# atmega16prog.net
KiCad netlist of a schematic drawn in EAGLE
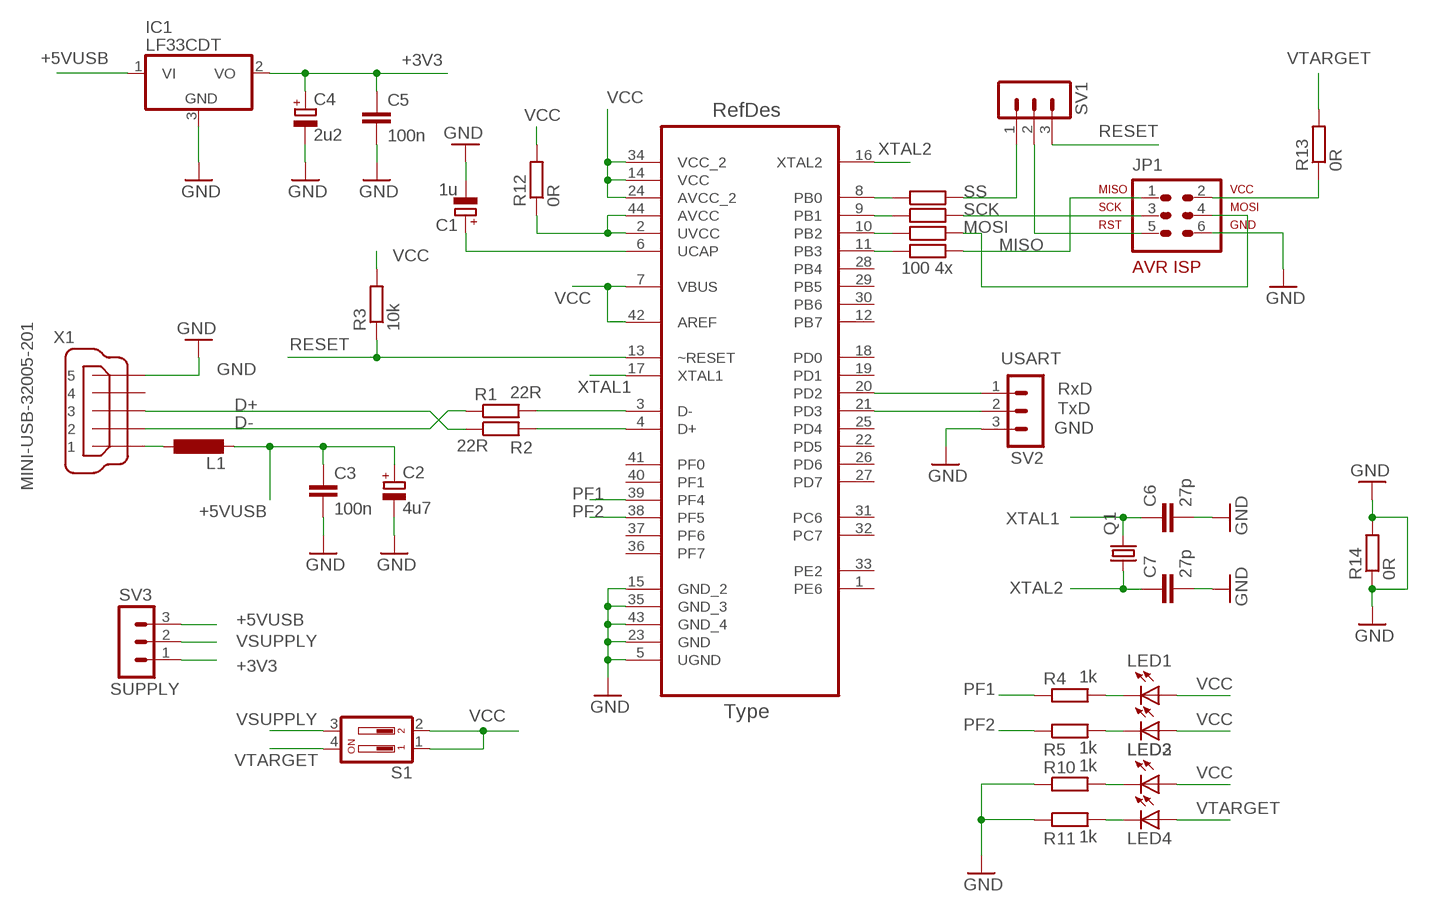
[diagram p0: schematic, sheet 1]

(export (version "E")
  (design (tool "Eeschema 10.0.6"))
  (components
    (comp (ref "C1")
      (value "1u")
      (footprint "eagle-import:SMC_A")
      (libsource (lib "eagle-import") (part "CPOL-EUSMCA"))
    )
    (comp (ref "C2")
      (value "4u7")
      (footprint "eagle-import:SMC_B")
      (libsource (lib "eagle-import") (part "resistor_CPOL-EUSMCB"))
    )
    (comp (ref "C3")
      (value "100n")
      (footprint "eagle-import:C0805K")
      (libsource (lib "eagle-import") (part "C-EUC0805K"))
    )
    (comp (ref "C4")
      (value "2u2")
      (footprint "eagle-import:A_3216-18W")
      (libsource (lib "eagle-import") (part "resistor_CPOL-EUA/3216-18W"))
    )
    (comp (ref "C5")
      (value "100n")
      (footprint "eagle-import:C0805K")
      (libsource (lib "eagle-import") (part "C-EUC0805K"))
    )
    (comp (ref "C6")
      (value "27p")
      (footprint "eagle-import:C0805K")
      (libsource (lib "eagle-import") (part "C-EUC0805K"))
    )
    (comp (ref "C7")
      (value "27p")
      (footprint "eagle-import:C0805K")
      (libsource (lib "eagle-import") (part "C-EUC0805K"))
    )
    (comp (ref "IC1")
      (value "LF33CDT")
      (footprint "eagle-import:TO252")
      (libsource (lib "eagle-import") (part "78DT05"))
    )
    (comp (ref "JP1")
      (value "AVR-ISP-6VERT")
      (footprint "eagle-import:AVR-ISP-6")
      (libsource (lib "eagle-import") (part "AVR-ISP-6VERT"))
    )
    (comp (ref "L1")
      (value "L-EU0204/7")
      (footprint "eagle-import:0204_7")
      (libsource (lib "eagle-import") (part "L-EU0204/7"))
    )
    (comp (ref "LED1")
      (value "LED3MM")
      (footprint "eagle-import:LED3MM")
      (libsource (lib "eagle-import") (part "LED3MM"))
    )
    (comp (ref "LED2")
      (value "LED3MM")
      (footprint "eagle-import:LED3MM")
      (libsource (lib "eagle-import") (part "LED3MM"))
    )
    (comp (ref "LED3")
      (value "LED3MM")
      (footprint "eagle-import:LED3MM")
      (libsource (lib "eagle-import") (part "LED3MM"))
    )
    (comp (ref "LED4")
      (value "LED3MM")
      (footprint "eagle-import:LED3MM")
      (libsource (lib "eagle-import") (part "LED3MM"))
    )
    (comp (ref "Q1")
      (value "CRYSTALHC49S")
      (footprint "eagle-import:HC49_S")
      (libsource (lib "eagle-import") (part "CRYSTALHC49S"))
    )
    (comp (ref "R1")
      (value "22R")
      (footprint "eagle-import:M0805")
      (libsource (lib "eagle-import") (part "R-EU_M0805"))
    )
    (comp (ref "R2")
      (value "22R")
      (footprint "eagle-import:M0805")
      (libsource (lib "eagle-import") (part "R-EU_M0805"))
    )
    (comp (ref "R3")
      (value "10k")
      (footprint "eagle-import:M0805")
      (libsource (lib "eagle-import") (part "R-EU_M0805"))
    )
    (comp (ref "R4")
      (value "1k")
      (footprint "eagle-import:M0805")
      (libsource (lib "eagle-import") (part "R-EU_M0805"))
    )
    (comp (ref "R5")
      (value "1k")
      (footprint "eagle-import:M0805")
      (libsource (lib "eagle-import") (part "R-EU_M0805"))
    )
    (comp (ref "R6")
      (value "100 4x")
      (footprint "eagle-import:M0805")
      (libsource (lib "eagle-import") (part "R-EU_M0805"))
    )
    (comp (ref "R7")
      (value "R-EU_R0805")
      (footprint "eagle-import:R0805")
      (libsource (lib "eagle-import") (part "R-EU_R0805"))
    )
    (comp (ref "R8")
      (value "R-EU_M0805")
      (footprint "eagle-import:M0805")
      (libsource (lib "eagle-import") (part "R-EU_M0805"))
    )
    (comp (ref "R9")
      (value "100")
      (footprint "eagle-import:M0805")
      (libsource (lib "eagle-import") (part "R-EU_M0805"))
    )
    (comp (ref "R10")
      (value "1k")
      (footprint "eagle-import:M0805")
      (libsource (lib "eagle-import") (part "R-EU_M0805"))
    )
    (comp (ref "R11")
      (value "1k")
      (footprint "eagle-import:M0805")
      (libsource (lib "eagle-import") (part "R-EU_M0805"))
    )
    (comp (ref "R12")
      (value "0R")
      (footprint "eagle-import:MINI_MELF-0102W")
      (libsource (lib "eagle-import") (part "R-EU_MELF0102W"))
    )
    (comp (ref "R13")
      (value "0R")
      (footprint "eagle-import:MINI_MELF-0102W")
      (libsource (lib "eagle-import") (part "R-EU_MELF0102W"))
    )
    (comp (ref "R14")
      (value "0R")
      (footprint "eagle-import:MINI_MELF-0102W")
      (libsource (lib "eagle-import") (part "R-EU_MELF0102W"))
    )
    (comp (ref "S1")
      (value "DS02")
      (footprint "eagle-import:DS-02")
      (libsource (lib "eagle-import") (part "DS02"))
    )
    (comp (ref "SV1")
      (value "MA03-1")
      (footprint "eagle-import:MA03-1")
      (libsource (lib "eagle-import") (part "MA03-1"))
    )
    (comp (ref "SV2")
      (value "MA03-1")
      (footprint "eagle-import:MA03-1")
      (libsource (lib "eagle-import") (part "MA03-1"))
    )
    (comp (ref "SV3")
      (value "MA03-1")
      (footprint "eagle-import:MA03-1")
      (libsource (lib "eagle-import") (part "MA03-1"))
    )
    (comp (ref "U1")
      (value "ATMEGA16U4-AU")
      (footprint "eagle-import:QFP80P1200X1200X120-44N")
      (libsource (lib "eagle-import") (part "ATMEGA16U4-AU"))
    )
    (comp (ref "X1")
      (value "MINI-USB-32005-201")
      (footprint "eagle-import:32005-201")
      (libsource (lib "eagle-import") (part "MINI-USB-32005-201"))
    )
  )
  (nets
    (net (code "1") (name "/+3V3") (class "Default")
      (node (ref "C4") (pin "+") (pinfunction "+_+") (pintype "passive"))
      (node (ref "C5") (pin "1") (pinfunction "1_1") (pintype "passive"))
      (node (ref "IC1") (pin "2") (pinfunction "VO_2") (pintype "passive"))
      (node (ref "SV3") (pin "1") (pinfunction "1_1") (pintype "passive"))
    )
    (net (code "2") (name "/+5VUSB") (class "Default")
      (node (ref "C2") (pin "+") (pinfunction "+_+") (pintype "passive"))
      (node (ref "C3") (pin "1") (pinfunction "1_1") (pintype "passive"))
      (node (ref "IC1") (pin "1") (pinfunction "VI_1") (pintype "input"))
      (node (ref "L1") (pin "2") (pinfunction "2_2") (pintype "passive"))
      (node (ref "SV3") (pin "3") (pinfunction "3_3") (pintype "passive"))
    )
    (net (code "3") (name "/D+") (class "Default")
      (node (ref "R2") (pin "1") (pinfunction "1_1") (pintype "passive"))
      (node (ref "X1") (pin "3") (pinfunction "3_3") (pintype "passive"))
    )
    (net (code "4") (name "/D-") (class "Default")
      (node (ref "R1") (pin "1") (pinfunction "1_1") (pintype "passive"))
      (node (ref "X1") (pin "2") (pinfunction "2_2") (pintype "passive"))
    )
    (net (code "5") (name "/MISO") (class "Default")
      (node (ref "JP1") (pin "1") (pinfunction "1_1") (pintype "passive"))
      (node (ref "R6") (pin "2") (pinfunction "2_2") (pintype "passive"))
    )
    (net (code "6") (name "/MOSI") (class "Default")
      (node (ref "JP1") (pin "4") (pinfunction "4_4") (pintype "passive"))
      (node (ref "R7") (pin "2") (pinfunction "2_2") (pintype "passive"))
    )
    (net (code "7") (name "/PF1") (class "Default")
      (node (ref "R4") (pin "1") (pinfunction "1_1") (pintype "passive"))
      (node (ref "U1") (pin "39") (pinfunction "PF4_39") (pintype "bidirectional"))
    )
    (net (code "8") (name "/PF2") (class "Default")
      (node (ref "R5") (pin "1") (pinfunction "1_1") (pintype "passive"))
      (node (ref "U1") (pin "38") (pinfunction "PF5_38") (pintype "bidirectional"))
    )
    (net (code "9") (name "/RESET") (class "Default")
      (node (ref "R3") (pin "1") (pinfunction "1_1") (pintype "passive"))
      (node (ref "SV1") (pin "3") (pinfunction "3_3") (pintype "passive"))
      (node (ref "U1") (pin "13") (pinfunction "~{RESET}_13") (pintype "input"))
    )
    (net (code "10") (name "/SCK") (class "Default")
      (node (ref "JP1") (pin "3") (pinfunction "3_3") (pintype "passive"))
      (node (ref "R8") (pin "2") (pinfunction "2_2") (pintype "passive"))
    )
    (net (code "11") (name "/SS") (class "Default")
      (node (ref "R9") (pin "2") (pinfunction "2_2") (pintype "passive"))
      (node (ref "SV1") (pin "1") (pinfunction "1_1") (pintype "passive"))
    )
    (net (code "12") (name "/VCC") (class "Default")
      (node (ref "LED1") (pin "A") (pinfunction "A_A") (pintype "passive"))
      (node (ref "LED2") (pin "A") (pinfunction "A_A") (pintype "passive"))
      (node (ref "LED3") (pin "A") (pinfunction "A_A") (pintype "passive"))
      (node (ref "R12") (pin "2") (pinfunction "2_2") (pintype "passive"))
      (node (ref "R3") (pin "2") (pinfunction "2_2") (pintype "passive"))
      (node (ref "S1") (pin "1") (pinfunction "1_1") (pintype "passive"))
      (node (ref "S1") (pin "2") (pinfunction "2_2") (pintype "passive"))
      (node (ref "U1") (pin "14") (pinfunction "VCC_14") (pintype "power_in"))
      (node (ref "U1") (pin "24") (pinfunction "AVCC_2_24") (pintype "power_in"))
      (node (ref "U1") (pin "34") (pinfunction "VCC_2_34") (pintype "power_in"))
      (node (ref "U1") (pin "42") (pinfunction "AREF_42") (pintype "input"))
      (node (ref "U1") (pin "7") (pinfunction "VBUS_7") (pintype "input"))
    )
    (net (code "13") (name "/VSUPPLY") (class "Default")
      (node (ref "S1") (pin "3") (pinfunction "3_3") (pintype "passive"))
      (node (ref "SV3") (pin "2") (pinfunction "2_2") (pintype "passive"))
    )
    (net (code "14") (name "/VTARGET") (class "Default")
      (node (ref "LED4") (pin "A") (pinfunction "A_A") (pintype "passive"))
      (node (ref "R13") (pin "2") (pinfunction "2_2") (pintype "passive"))
      (node (ref "S1") (pin "4") (pinfunction "4_4") (pintype "passive"))
    )
    (net (code "15") (name "/XTAL1") (class "Default")
      (node (ref "C6") (pin "1") (pinfunction "1_1") (pintype "passive"))
      (node (ref "Q1") (pin "2") (pinfunction "2_2") (pintype "passive"))
      (node (ref "U1") (pin "17") (pinfunction "XTAL1_17") (pintype "input"))
    )
    (net (code "16") (name "/XTAL2") (class "Default")
      (node (ref "C7") (pin "1") (pinfunction "1_1") (pintype "passive"))
      (node (ref "Q1") (pin "1") (pinfunction "1_1") (pintype "passive"))
      (node (ref "U1") (pin "16") (pinfunction "XTAL2_16") (pintype "output"))
    )
    (net (code "17") (name "GND") (class "Default")
      (node (ref "C1") (pin "-") (pinfunction "-_-") (pintype "passive"))
      (node (ref "C2") (pin "-") (pinfunction "-_-") (pintype "passive"))
      (node (ref "C3") (pin "2") (pinfunction "2_2") (pintype "passive"))
      (node (ref "C4") (pin "-") (pinfunction "-_-") (pintype "passive"))
      (node (ref "C5") (pin "2") (pinfunction "2_2") (pintype "passive"))
      (node (ref "C6") (pin "2") (pinfunction "2_2") (pintype "passive"))
      (node (ref "C7") (pin "2") (pinfunction "2_2") (pintype "passive"))
      (node (ref "IC1") (pin "3") (pinfunction "GND_3") (pintype "passive"))
      (node (ref "JP1") (pin "6") (pinfunction "6_6") (pintype "passive"))
      (node (ref "R10") (pin "1") (pinfunction "1_1") (pintype "passive"))
      (node (ref "R11") (pin "1") (pinfunction "1_1") (pintype "passive"))
      (node (ref "R14") (pin "1") (pinfunction "1_1") (pintype "passive"))
      (node (ref "R14") (pin "2") (pinfunction "2_2") (pintype "passive"))
      (node (ref "SV2") (pin "3") (pinfunction "3_3") (pintype "passive"))
      (node (ref "U1") (pin "15") (pinfunction "GND_2_15") (pintype "passive"))
      (node (ref "U1") (pin "23") (pinfunction "GND_23") (pintype "passive"))
      (node (ref "U1") (pin "35") (pinfunction "GND_3_35") (pintype "passive"))
      (node (ref "U1") (pin "43") (pinfunction "GND_4_43") (pintype "passive"))
      (node (ref "U1") (pin "5") (pinfunction "UGND_5") (pintype "passive"))
      (node (ref "X1") (pin "5") (pinfunction "5_5") (pintype "passive"))
    )
    (net (code "18") (name "Net-(JP1-Pad2)") (class "Default")
      (node (ref "JP1") (pin "2") (pinfunction "2_2") (pintype "passive"))
      (node (ref "R13") (pin "1") (pinfunction "1_1") (pintype "passive"))
    )
    (net (code "19") (name "Net-(JP1-Pad5)") (class "Default")
      (node (ref "JP1") (pin "5") (pinfunction "5_5") (pintype "passive"))
      (node (ref "SV1") (pin "2") (pinfunction "2_2") (pintype "passive"))
    )
    (net (code "20") (name "Net-(L1-Pad1)") (class "Default")
      (node (ref "L1") (pin "1") (pinfunction "1_1") (pintype "passive"))
      (node (ref "X1") (pin "1") (pinfunction "1_1") (pintype "passive"))
    )
    (net (code "21") (name "Net-(LED1-C)") (class "Default")
      (node (ref "LED1") (pin "K") (pinfunction "C_K") (pintype "passive"))
      (node (ref "R4") (pin "2") (pinfunction "2_2") (pintype "passive"))
    )
    (net (code "22") (name "Net-(LED2-C)") (class "Default")
      (node (ref "LED2") (pin "K") (pinfunction "C_K") (pintype "passive"))
      (node (ref "R5") (pin "2") (pinfunction "2_2") (pintype "passive"))
    )
    (net (code "23") (name "Net-(LED3-C)") (class "Default")
      (node (ref "LED3") (pin "K") (pinfunction "C_K") (pintype "passive"))
      (node (ref "R10") (pin "2") (pinfunction "2_2") (pintype "passive"))
    )
    (net (code "24") (name "Net-(LED4-C)") (class "Default")
      (node (ref "LED4") (pin "K") (pinfunction "C_K") (pintype "passive"))
      (node (ref "R11") (pin "2") (pinfunction "2_2") (pintype "passive"))
    )
    (net (code "25") (name "Net-(U1-AVCC)") (class "Default")
      (node (ref "R12") (pin "1") (pinfunction "1_1") (pintype "passive"))
      (node (ref "U1") (pin "2") (pinfunction "UVCC_2") (pintype "power_in"))
      (node (ref "U1") (pin "44") (pinfunction "AVCC_44") (pintype "power_in"))
    )
    (net (code "26") (name "Net-(U1-D+)") (class "Default")
      (node (ref "R2") (pin "2") (pinfunction "2_2") (pintype "passive"))
      (node (ref "U1") (pin "4") (pinfunction "D+_4") (pintype "passive"))
    )
    (net (code "27") (name "Net-(U1-D-)") (class "Default")
      (node (ref "R1") (pin "2") (pinfunction "2_2") (pintype "passive"))
      (node (ref "U1") (pin "3") (pinfunction "D-_3") (pintype "passive"))
    )
    (net (code "28") (name "Net-(U1-PB0)") (class "Default")
      (node (ref "R9") (pin "1") (pinfunction "1_1") (pintype "passive"))
      (node (ref "U1") (pin "8") (pinfunction "PB0_8") (pintype "bidirectional"))
    )
    (net (code "29") (name "Net-(U1-PB1)") (class "Default")
      (node (ref "R8") (pin "1") (pinfunction "1_1") (pintype "passive"))
      (node (ref "U1") (pin "9") (pinfunction "PB1_9") (pintype "bidirectional"))
    )
    (net (code "30") (name "Net-(U1-PB2)") (class "Default")
      (node (ref "R7") (pin "1") (pinfunction "1_1") (pintype "passive"))
      (node (ref "U1") (pin "10") (pinfunction "PB2_10") (pintype "bidirectional"))
    )
    (net (code "31") (name "Net-(U1-PB3)") (class "Default")
      (node (ref "R6") (pin "1") (pinfunction "1_1") (pintype "passive"))
      (node (ref "U1") (pin "11") (pinfunction "PB3_11") (pintype "bidirectional"))
    )
    (net (code "32") (name "Net-(U1-PD2)") (class "Default")
      (node (ref "SV2") (pin "1") (pinfunction "1_1") (pintype "passive"))
      (node (ref "U1") (pin "20") (pinfunction "PD2_20") (pintype "bidirectional"))
    )
    (net (code "33") (name "Net-(U1-PD3)") (class "Default")
      (node (ref "SV2") (pin "2") (pinfunction "2_2") (pintype "passive"))
      (node (ref "U1") (pin "21") (pinfunction "PD3_21") (pintype "bidirectional"))
    )
    (net (code "34") (name "Net-(U1-UCAP)") (class "Default")
      (node (ref "C1") (pin "+") (pinfunction "+_+") (pintype "passive"))
      (node (ref "U1") (pin "6") (pinfunction "UCAP_6") (pintype "power_in"))
    )
    (net (code "35") (name "unconnected-(U1-PB4-Pad28)") (class "Default")
      (node (ref "U1") (pin "28") (pinfunction "PB4_28") (pintype "bidirectional"))
    )
    (net (code "36") (name "unconnected-(U1-PB5-Pad29)") (class "Default")
      (node (ref "U1") (pin "29") (pinfunction "PB5_29") (pintype "bidirectional"))
    )
    (net (code "37") (name "unconnected-(U1-PB6-Pad30)") (class "Default")
      (node (ref "U1") (pin "30") (pinfunction "PB6_30") (pintype "bidirectional"))
    )
    (net (code "38") (name "unconnected-(U1-PB7-Pad12)") (class "Default")
      (node (ref "U1") (pin "12") (pinfunction "PB7_12") (pintype "bidirectional"))
    )
    (net (code "39") (name "unconnected-(U1-PC6-Pad31)") (class "Default")
      (node (ref "U1") (pin "31") (pinfunction "PC6_31") (pintype "bidirectional"))
    )
    (net (code "40") (name "unconnected-(U1-PC7-Pad32)") (class "Default")
      (node (ref "U1") (pin "32") (pinfunction "PC7_32") (pintype "bidirectional"))
    )
    (net (code "41") (name "unconnected-(U1-PD0-Pad18)") (class "Default")
      (node (ref "U1") (pin "18") (pinfunction "PD0_18") (pintype "bidirectional"))
    )
    (net (code "42") (name "unconnected-(U1-PD1-Pad19)") (class "Default")
      (node (ref "U1") (pin "19") (pinfunction "PD1_19") (pintype "bidirectional"))
    )
    (net (code "43") (name "unconnected-(U1-PD4-Pad25)") (class "Default")
      (node (ref "U1") (pin "25") (pinfunction "PD4_25") (pintype "bidirectional"))
    )
    (net (code "44") (name "unconnected-(U1-PD5-Pad22)") (class "Default")
      (node (ref "U1") (pin "22") (pinfunction "PD5_22") (pintype "bidirectional"))
    )
    (net (code "45") (name "unconnected-(U1-PD6-Pad26)") (class "Default")
      (node (ref "U1") (pin "26") (pinfunction "PD6_26") (pintype "bidirectional"))
    )
    (net (code "46") (name "unconnected-(U1-PD7-Pad27)") (class "Default")
      (node (ref "U1") (pin "27") (pinfunction "PD7_27") (pintype "bidirectional"))
    )
    (net (code "47") (name "unconnected-(U1-PE2-Pad33)") (class "Default")
      (node (ref "U1") (pin "33") (pinfunction "PE2_33") (pintype "bidirectional"))
    )
    (net (code "48") (name "unconnected-(U1-PE6-Pad1)") (class "Default")
      (node (ref "U1") (pin "1") (pinfunction "PE6_1") (pintype "bidirectional"))
    )
    (net (code "49") (name "unconnected-(U1-PF0-Pad41)") (class "Default")
      (node (ref "U1") (pin "41") (pinfunction "PF0_41") (pintype "bidirectional"))
    )
    (net (code "50") (name "unconnected-(U1-PF1-Pad40)") (class "Default")
      (node (ref "U1") (pin "40") (pinfunction "PF1_40") (pintype "bidirectional"))
    )
    (net (code "51") (name "unconnected-(U1-PF6-Pad37)") (class "Default")
      (node (ref "U1") (pin "37") (pinfunction "PF6_37") (pintype "bidirectional"))
    )
    (net (code "52") (name "unconnected-(U1-PF7-Pad36)") (class "Default")
      (node (ref "U1") (pin "36") (pinfunction "PF7_36") (pintype "bidirectional"))
    )
    (net (code "53") (name "unconnected-(X1-Pad4)") (class "Default")
      (node (ref "X1") (pin "4") (pinfunction "4_4") (pintype "passive"))
    )
  )
)
